# USB.net
KiCad netlist of a schematic drawn in Altium Designer
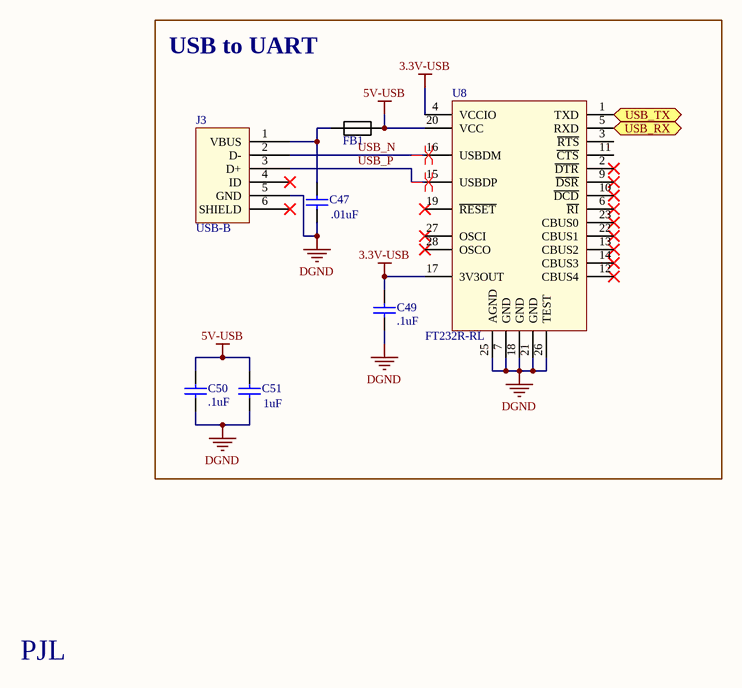
[diagram p0: USB.SchDoc]

(export (version "E")
  (design (tool "Eeschema 10.0.6"))
  (components
    (comp (ref "C47")
      (value ".01uF")
      (footprint "Passives:CAPC1608XL")
      (description "CAP CER 10000PF 16V 10% X7R 0603")
      (fields
        (field (name "MANUFACTURER PART NUMBER") "GRM188R71C103KA01D")
        (field (name "MANUFACTURER") "Murata Electronics North America")
      )
      (libsource (lib "MyLibraries") (part "Capacitor"))
    )
    (comp (ref "C49")
      (value ".1uF")
      (footprint "CAPC1608XN")
      (description "CAP CER 0.1UF 10V 20% X7R 0603")
      (fields (field (name "MANUFACTURER PART NUMBER") "CX0603MRX7R6BB104") (field (name "TOLERANCE") "±20%"))
      (libsource (lib "Any") (part "CAP-CERAMIC-NP"))
    )
    (comp (ref "C50")
      (value ".1uF")
      (footprint "CAPC1608XN")
      (description "CAP CER 0.1UF 10V 20% X7R 0603")
      (fields (field (name "MANUFACTURER PART NUMBER") "CX0603MRX7R6BB104") (field (name "TOLERANCE") "±20%"))
      (libsource (lib "Any") (part "CAP-CERAMIC-NP"))
    )
    (comp (ref "C51")
      (value "1uF")
      (footprint "Passives:CAPC1608XN")
      (description "CAP CER 1UF 10V 10% X7R 0603")
      (fields
        (field (name "MANUFACTURER PART NUMBER") "GRM188R71A105KA61D")
        (field (name "TOLERANCE") "±10%")
      )
      (libsource (lib "MyLibraries") (part "Capacitor"))
    )
    (comp (ref "FB1")
      (value "FERRITE")
      (footprint "MyAltiumLibrary:RESC2012X06N/0805")
      (description "FERRITE BEAD 60 OHM 3.0A 0805")
      (fields
        (field (name "MANUFACTURER") "Wurth Electronics Inc")
        (field (name "MANUFACTURER PART NUMBER") "742792063")
      )
      (libsource (lib "MyLibraries") (part "FERRITE"))
    )
    (comp (ref "J3")
      (value "USB-B")
      (footprint "USB-MiniB-90")
      (description "CONN MINI USB RCPT RA TYPE B SMD")
      (fields
        (field (name "MANUFACTURER") "TE Connectivity")
        (field (name "MANUFACTURER PART NUMBER") "1734035-2")
      )
      (libsource (lib "MyAltiumLibrary") (part "USB-B"))
    )
    (comp (ref "U8")
      (value "FT232R-RL")
      (footprint "MyAltiumLibrary:SOP65P780X200-28L")
      (description "IC USB FS SERIAL UART 28-SSOP")
      (fields
        (field (name "MANUFACTURER") "FTDI, Future Technology Devices International Ltd")
        (field (name "MANUFACTURER PART NUMBER") "FT232RL-REEL")
      )
      (libsource (lib "MyLibraries") (part "FT232R-RL"))
    )
  )
  (nets
    (net (code "1") (name "/USB_N") (class "Default")
      (node (ref "J3") (pin "2") (pinfunction "D-_2") (pintype "passive"))
      (node (ref "U8") (pin "16") (pinfunction "USBDM_16") (pintype "passive"))
    )
    (net (code "2") (name "/USB_P") (class "Default")
      (node (ref "J3") (pin "3") (pinfunction "D+_3") (pintype "passive"))
      (node (ref "U8") (pin "15") (pinfunction "USBDP_15") (pintype "passive"))
    )
    (net (code "3") (name "/USB_RX") (class "Default")
      (node (ref "U8") (pin "5") (pinfunction "RXD_5") (pintype "passive"))
    )
    (net (code "4") (name "/USB_TX") (class "Default")
      (node (ref "U8") (pin "1") (pinfunction "TXD_1") (pintype "passive"))
    )
    (net (code "5") (name "3.3V-USB") (class "Default")
      (node (ref "C49") (pin "2") (pinfunction "2_2") (pintype "passive"))
      (node (ref "U8") (pin "17") (pinfunction "3V3OUT_17") (pintype "passive"))
      (node (ref "U8") (pin "4") (pinfunction "VCCIO_4") (pintype "passive"))
    )
    (net (code "6") (name "5V-USB") (class "Default")
      (node (ref "C50") (pin "2") (pinfunction "2_2") (pintype "passive"))
      (node (ref "C51") (pin "2") (pinfunction "2_2") (pintype "passive"))
      (node (ref "FB1") (pin "2") (pinfunction "2_2") (pintype "passive"))
      (node (ref "U8") (pin "20") (pinfunction "VCC_20") (pintype "passive"))
    )
    (net (code "7") (name "DGND") (class "Default")
      (node (ref "C47") (pin "1") (pinfunction "1_1") (pintype "passive"))
      (node (ref "C49") (pin "1") (pinfunction "1_1") (pintype "passive"))
      (node (ref "C50") (pin "1") (pinfunction "1_1") (pintype "passive"))
      (node (ref "C51") (pin "1") (pinfunction "1_1") (pintype "passive"))
      (node (ref "J3") (pin "5") (pinfunction "GND_5") (pintype "passive"))
      (node (ref "U8") (pin "18") (pinfunction "GND_18") (pintype "passive"))
      (node (ref "U8") (pin "21") (pinfunction "GND_21") (pintype "passive"))
      (node (ref "U8") (pin "25") (pinfunction "AGND_25") (pintype "passive"))
      (node (ref "U8") (pin "26") (pinfunction "TEST_26") (pintype "passive"))
      (node (ref "U8") (pin "7") (pinfunction "GND_7") (pintype "passive"))
    )
    (net (code "8") (name "Net-(J3-VBUS)") (class "Default")
      (node (ref "C47") (pin "2") (pinfunction "2_2") (pintype "passive"))
      (node (ref "FB1") (pin "1") (pinfunction "1_1") (pintype "passive"))
      (node (ref "J3") (pin "1") (pinfunction "VBUS_1") (pintype "passive"))
    )
    (net (code "9") (name "unconnected-(J3-ID-Pad4)") (class "Default")
      (node (ref "J3") (pin "4") (pinfunction "ID_4") (pintype "passive+no_connect"))
    )
    (net (code "10") (name "unconnected-(J3-SHIELD-Pad6)") (class "Default")
      (node (ref "J3") (pin "6") (pinfunction "SHIELD_6") (pintype "passive+no_connect"))
    )
    (net (code "11") (name "unconnected-(U8-CBUS0-Pad23)") (class "Default")
      (node (ref "U8") (pin "23") (pinfunction "CBUS0_23") (pintype "passive+no_connect"))
    )
    (net (code "12") (name "unconnected-(U8-CBUS1-Pad22)") (class "Default")
      (node (ref "U8") (pin "22") (pinfunction "CBUS1_22") (pintype "passive+no_connect"))
    )
    (net (code "13") (name "unconnected-(U8-CBUS2-Pad13)") (class "Default")
      (node (ref "U8") (pin "13") (pinfunction "CBUS2_13") (pintype "passive+no_connect"))
    )
    (net (code "14") (name "unconnected-(U8-CBUS3-Pad14)") (class "Default")
      (node (ref "U8") (pin "14") (pinfunction "CBUS3_14") (pintype "passive+no_connect"))
    )
    (net (code "15") (name "unconnected-(U8-CBUS4-Pad12)") (class "Default")
      (node (ref "U8") (pin "12") (pinfunction "CBUS4_12") (pintype "passive+no_connect"))
    )
    (net (code "16") (name "unconnected-(U8-OSCI-Pad27)") (class "Default")
      (node (ref "U8") (pin "27") (pinfunction "OSCI_27") (pintype "passive+no_connect"))
    )
    (net (code "17") (name "unconnected-(U8-OSCO-Pad28)") (class "Default")
      (node (ref "U8") (pin "28") (pinfunction "OSCO_28") (pintype "passive+no_connect"))
    )
    (net (code "18") (name "unconnected-(U8-~{CTS}-Pad11)") (class "Default")
      (node (ref "U8") (pin "11") (pinfunction "~{CTS}_11") (pintype "passive"))
    )
    (net (code "19") (name "unconnected-(U8-~{DCD}-Pad10)") (class "Default")
      (node (ref "U8") (pin "10") (pinfunction "~{DCD}_10") (pintype "passive+no_connect"))
    )
    (net (code "20") (name "unconnected-(U8-~{DSR}-Pad9)") (class "Default")
      (node (ref "U8") (pin "9") (pinfunction "~{DSR}_9") (pintype "passive+no_connect"))
    )
    (net (code "21") (name "unconnected-(U8-~{DTR}-Pad2)") (class "Default")
      (node (ref "U8") (pin "2") (pinfunction "~{DTR}_2") (pintype "passive+no_connect"))
    )
    (net (code "22") (name "unconnected-(U8-~{RESET}-Pad19)") (class "Default")
      (node (ref "U8") (pin "19") (pinfunction "~{RESET}_19") (pintype "passive+no_connect"))
    )
    (net (code "23") (name "unconnected-(U8-~{RI}-Pad6)") (class "Default")
      (node (ref "U8") (pin "6") (pinfunction "~{RI}_6") (pintype "passive+no_connect"))
    )
    (net (code "24") (name "unconnected-(U8-~{RTS}-Pad3)") (class "Default")
      (node (ref "U8") (pin "3") (pinfunction "~{RTS}_3") (pintype "passive"))
    )
  )
)
